# BoardDiagramEntryConn.net
KiCad netlist of a schematic drawn in Altium Designer
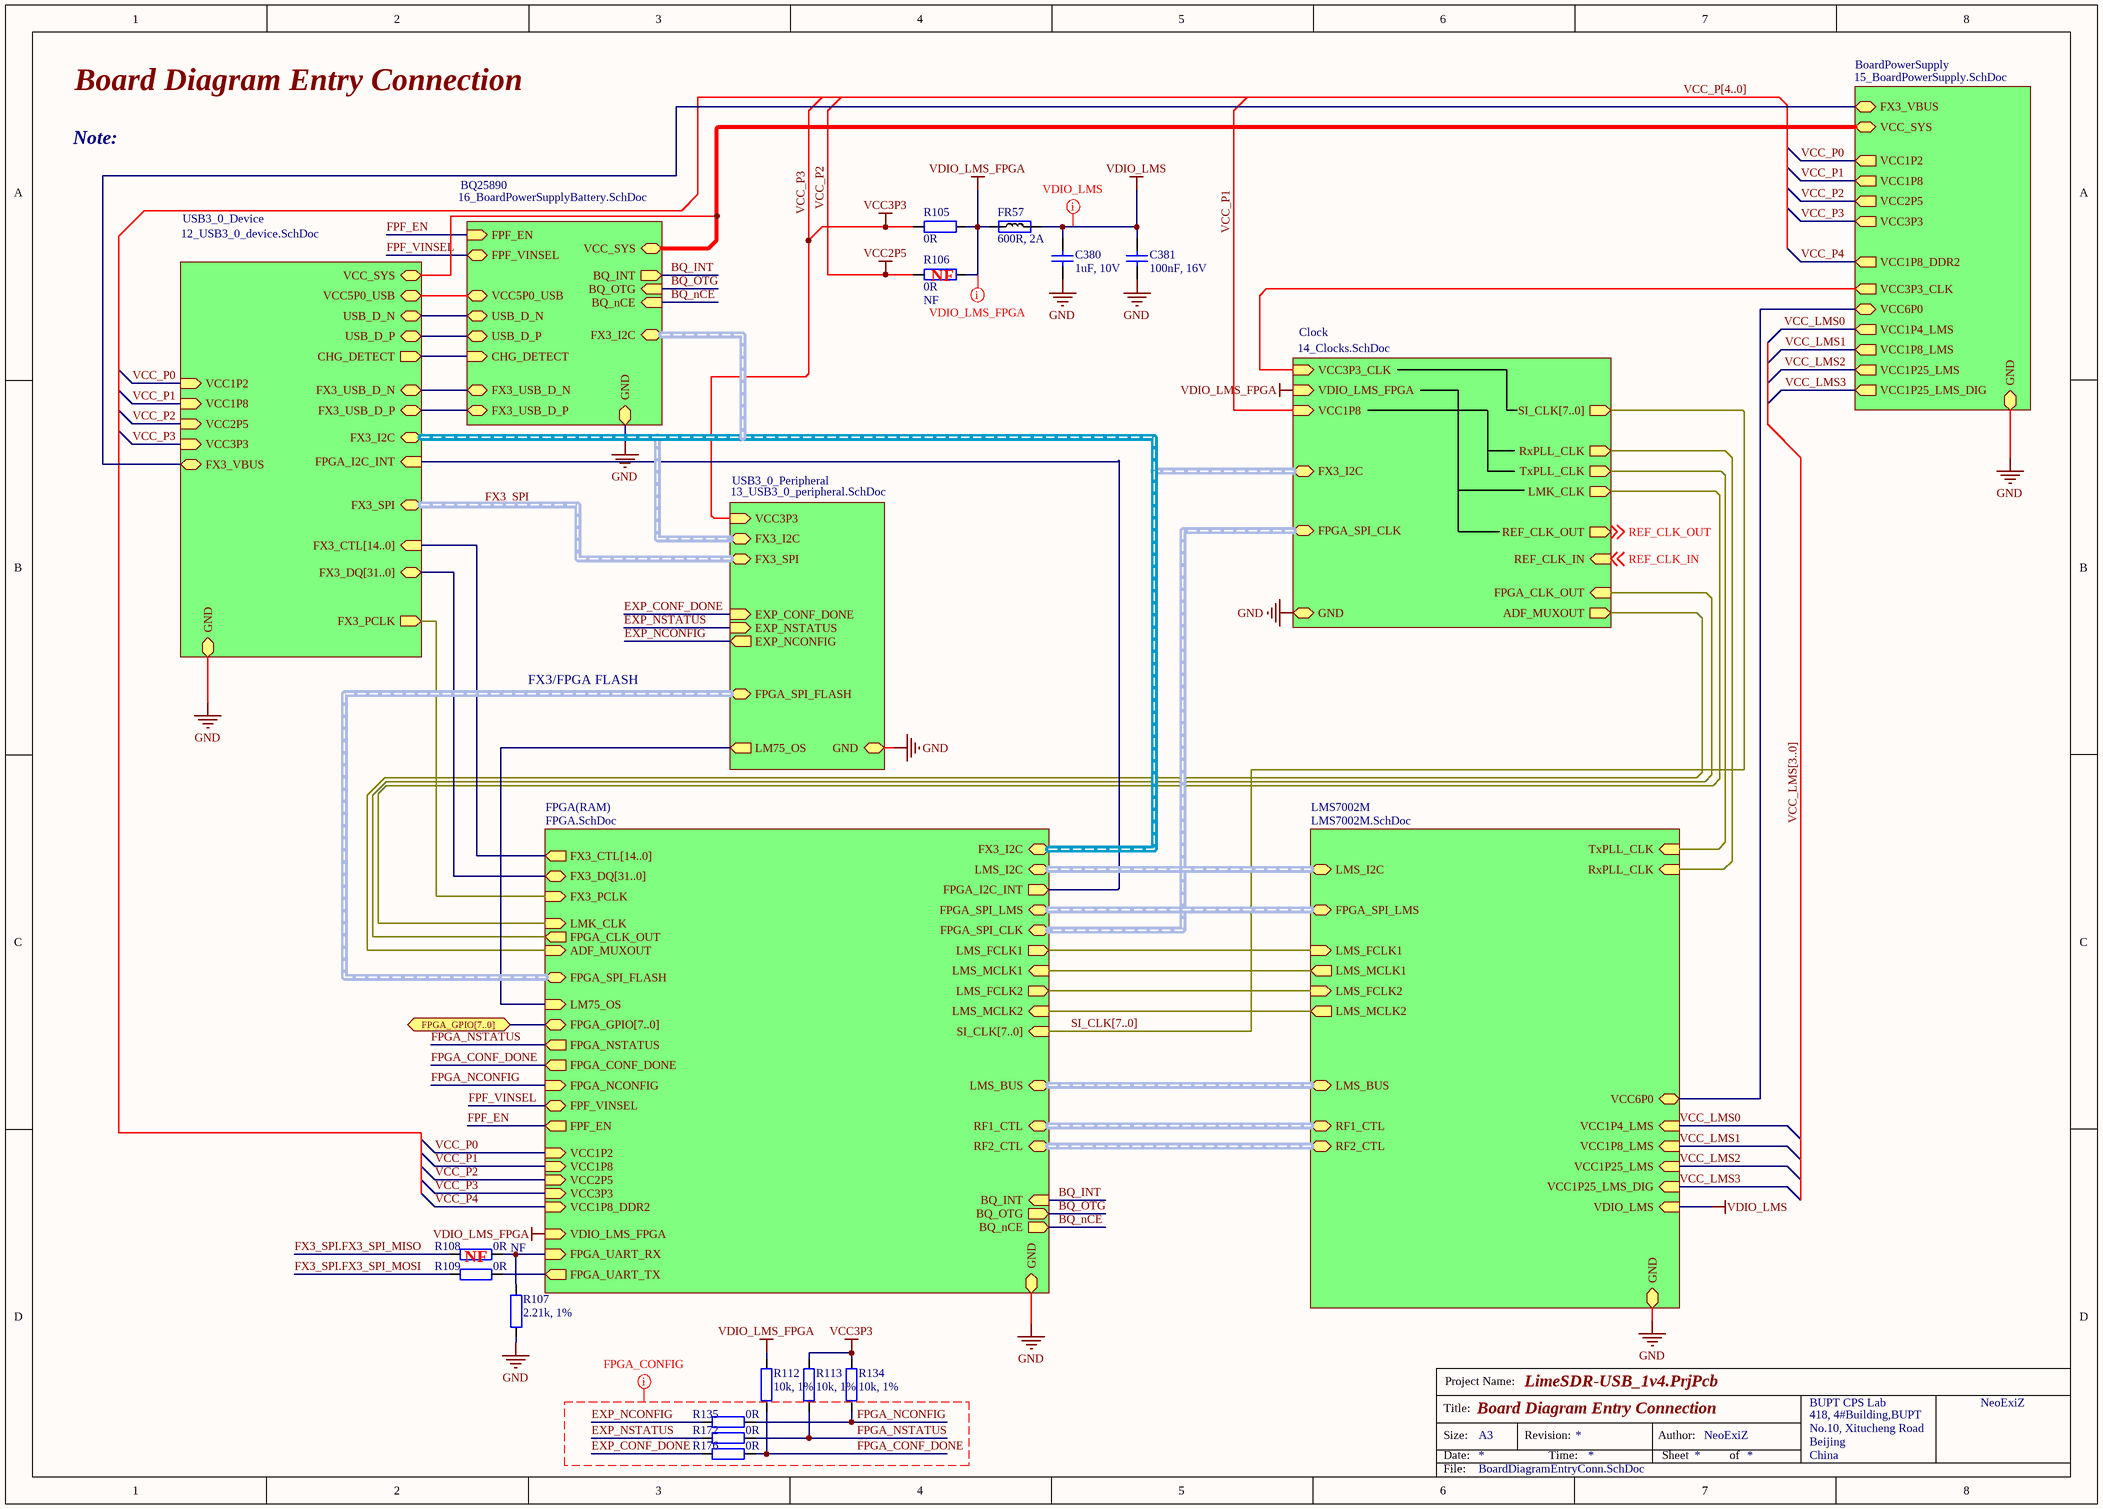
[diagram p0: BoardDiagramEntryConn.SchDoc]

(export (version "E")
  (design (tool "Eeschema 10.0.6"))
  (components
    (comp (ref "C380")
      (value "1uF, 10V")
      (footprint "CAP0402")
      (fields (field (name "MANUFACTURER") "TDK"))
      (libsource (lib "LimeMicroAltiumLib_schLib") (part "Cap_0402"))
    )
    (comp (ref "C381")
      (value "100nF, 16V")
      (footprint "CAP0402")
      (fields
        (field (name "MANUFACTURER") "Murata Electronics")
        (field (name "TOLERANCE") "10 %")
        (field (name "MANUFACTURER PART NUMBER") "GRM155R71C104KA88D")
      )
      (libsource (lib "LimeMicroAltiumLib_schLib") (part "Cap_0402"))
    )
    (comp (ref "FR57")
      (value "600R, 2A")
      (footprint "RES0805")
      (fields (field (name "MANUFACTURER") "TDK Corporation"))
      (libsource (lib "LimeMicroAltiumLib_schLib") (part "Ferrite"))
    )
    (comp (ref "R105")
      (value "0R")
      (footprint "RES0402")
      (fields (field (name "MANUFACTURER") "Yageo") (field (name "TOLERANCE") "Jumper"))
      (libsource (lib "LimeMicroAltiumLib_schLib") (part "Res_0402"))
    )
    (comp (ref "R106")
      (value "0R")
      (footprint "RES0402")
      (fields
        (field (name "ASSEMBLY INFO") "NF")
        (field (name "MANUFACTURER") "Yageo")
        (field (name "TOLERANCE") "Jumper")
      )
      (libsource (lib "LimeMicroAltiumLib_schLib") (part "Res_0402"))
    )
    (comp (ref "R107")
      (value "2.21k, 1%")
      (footprint "RES0402")
      (fields (field (name "MANUFACTURER") "Stackpole Electronics Inc.") (field (name "TOLERANCE") "±1%"))
      (libsource (lib "LimeMicroAltiumLib_schLib") (part "Res_0402"))
    )
    (comp (ref "R108")
      (value "0R")
      (footprint "RES0402")
      (fields (field (name "MANUFACTURER") "Yageo") (field (name "ASSEMBLY INFO") "NF"))
      (libsource (lib "LimeFPGAboard_schLib") (part "Res_0402"))
    )
    (comp (ref "R109")
      (value "0R")
      (footprint "RES0402")
      (fields (field (name "MANUFACTURER") "Yageo"))
      (libsource (lib "LimeFPGAboard_schLib") (part "Res_0402"))
    )
    (comp (ref "R112")
      (value "10k, 1%")
      (footprint "RES0402")
      (fields (field (name "MANUFACTURER") "Yageo") (field (name "TOLERANCE") "±1%"))
      (libsource (lib "LimeMicroAltiumLib_schLib") (part "Res_0402"))
    )
    (comp (ref "R113")
      (value "10k, 1%")
      (footprint "RES0402")
      (fields (field (name "MANUFACTURER") "Yageo") (field (name "TOLERANCE") "±1%"))
      (libsource (lib "LimeMicroAltiumLib_schLib") (part "Res_0402"))
    )
    (comp (ref "R134")
      (value "10k, 1%")
      (footprint "RES0402")
      (fields (field (name "MANUFACTURER") "Yageo") (field (name "TOLERANCE") "±1%"))
      (libsource (lib "LimeMicroAltiumLib_schLib") (part "Res_0402"))
    )
    (comp (ref "R135")
      (value "0R")
      (footprint "RES0402")
      (fields (field (name "MANUFACTURER") "Yageo"))
      (libsource (lib "LimeFPGAboard_schLib") (part "Res_0402"))
    )
    (comp (ref "R172")
      (value "0R")
      (footprint "RES0402")
      (fields (field (name "MANUFACTURER") "Yageo"))
      (libsource (lib "LimeFPGAboard_schLib") (part "Res_0402"))
    )
    (comp (ref "R176")
      (value "0R")
      (footprint "RES0402")
      (fields (field (name "MANUFACTURER") "Yageo"))
      (libsource (lib "LimeFPGAboard_schLib") (part "Res_0402"))
    )
  )
  (nets
    (net (code "23") (name "/EXP_CONF_DONE") (class "Default")
      (node (ref "R176") (pin "1") (pinfunction "1_1") (pintype "passive"))
    )
    (net (code "24") (name "/EXP_NCONFIG") (class "Default")
      (node (ref "R135") (pin "1") (pinfunction "1_1") (pintype "passive"))
    )
    (net (code "25") (name "/EXP_NSTATUS") (class "Default")
      (node (ref "R172") (pin "1") (pinfunction "1_1") (pintype "passive"))
    )
    (net (code "29") (name "/FPGA_CONF_DONE") (class "Default")
      (node (ref "R112") (pin "2") (pinfunction "2_2") (pintype "passive"))
      (node (ref "R176") (pin "2") (pinfunction "2_2") (pintype "passive"))
    )
    (net (code "32") (name "/FPGA_NCONFIG") (class "Default")
      (node (ref "R134") (pin "2") (pinfunction "2_2") (pintype "passive"))
      (node (ref "R135") (pin "2") (pinfunction "2_2") (pintype "passive"))
    )
    (net (code "33") (name "/FPGA_NSTATUS") (class "Default")
      (node (ref "R113") (pin "2") (pinfunction "2_2") (pintype "passive"))
      (node (ref "R172") (pin "2") (pinfunction "2_2") (pintype "passive"))
    )
    (net (code "37") (name "/FPGA_UART_RX") (class "Default")
      (node (ref "R107") (pin "2") (pinfunction "2_2") (pintype "passive"))
      (node (ref "R108") (pin "2") (pinfunction "2_2") (pintype "passive"))
    )
    (net (code "38") (name "/FPGA_UART_TX") (class "Default")
      (node (ref "R109") (pin "2") (pinfunction "2_2") (pintype "passive"))
    )
    (net (code "43") (name "/FX3_SPI.FX3_SPI_MISO") (class "Default")
      (node (ref "R108") (pin "1") (pinfunction "1_1") (pintype "passive"))
    )
    (net (code "44") (name "/FX3_SPI.FX3_SPI_MOSI") (class "Default")
      (node (ref "R109") (pin "1") (pinfunction "1_1") (pintype "passive"))
    )
    (net (code "77") (name "GND") (class "Default")
      (node (ref "C380") (pin "1") (pinfunction "1_1") (pintype "passive"))
      (node (ref "C381") (pin "2") (pinfunction "2_2") (pintype "passive"))
      (node (ref "R107") (pin "1") (pinfunction "1_1") (pintype "passive"))
    )
    (net (code "80") (name "VCC2P5") (class "Default")
      (node (ref "R106") (pin "2") (pinfunction "2_2") (pintype "passive"))
    )
    (net (code "81") (name "VCC3P3") (class "Default")
      (node (ref "R105") (pin "2") (pinfunction "2_2") (pintype "passive"))
      (node (ref "R113") (pin "1") (pinfunction "1_1") (pintype "passive"))
      (node (ref "R134") (pin "1") (pinfunction "1_1") (pintype "passive"))
    )
    (net (code "82") (name "VDIO_LMS") (class "Default")
      (node (ref "C380") (pin "2") (pinfunction "2_2") (pintype "passive"))
      (node (ref "C381") (pin "1") (pinfunction "1_1") (pintype "passive"))
      (node (ref "FR57") (pin "2") (pinfunction "2_2") (pintype "passive"))
    )
    (net (code "83") (name "VDIO_LMS_FPGA") (class "Default")
      (node (ref "FR57") (pin "1") (pinfunction "1_1") (pintype "passive"))
      (node (ref "R105") (pin "1") (pinfunction "1_1") (pintype "passive"))
      (node (ref "R106") (pin "1") (pinfunction "1_1") (pintype "passive"))
      (node (ref "R112") (pin "1") (pinfunction "1_1") (pintype "passive"))
    )
  )
)
